# SpheroRemote.net
KiCad netlist of a schematic drawn in EAGLE
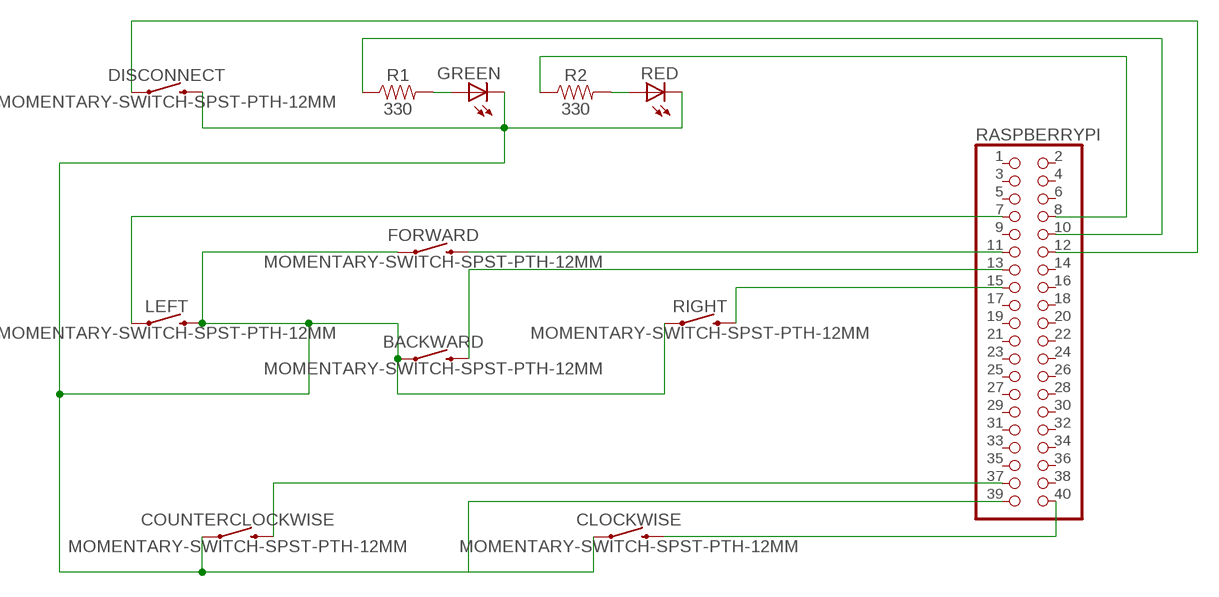
[diagram p0: schematic, sheet 1]

(export (version "E")
  (design (tool "Eeschema 10.0.6"))
  (components
    (comp (ref "BACKWARD")
      (value "MOMENTARY-SWITCH-SPST-PTH-12MM")
      (footprint "eagle-import:TACTILE_SWITCH_PTH_12MM")
      (libsource (lib "eagle-import") (part "MOMENTARY-SWITCH-SPST-PTH-12MM"))
    )
    (comp (ref "CLOCKWISE")
      (value "MOMENTARY-SWITCH-SPST-PTH-12MM")
      (footprint "eagle-import:TACTILE_SWITCH_PTH_12MM")
      (libsource (lib "eagle-import") (part "MOMENTARY-SWITCH-SPST-PTH-12MM"))
    )
    (comp (ref "COUNTERCLOCKWISE")
      (value "MOMENTARY-SWITCH-SPST-PTH-12MM")
      (footprint "eagle-import:TACTILE_SWITCH_PTH_12MM")
      (libsource (lib "eagle-import") (part "MOMENTARY-SWITCH-SPST-PTH-12MM"))
    )
    (comp (ref "DISCONNECT")
      (value "MOMENTARY-SWITCH-SPST-PTH-12MM")
      (footprint "eagle-import:TACTILE_SWITCH_PTH_12MM")
      (libsource (lib "eagle-import") (part "MOMENTARY-SWITCH-SPST-PTH-12MM"))
    )
    (comp (ref "FORWARD")
      (value "MOMENTARY-SWITCH-SPST-PTH-12MM")
      (footprint "eagle-import:TACTILE_SWITCH_PTH_12MM")
      (libsource (lib "eagle-import") (part "MOMENTARY-SWITCH-SPST-PTH-12MM"))
    )
    (comp (ref "GREEN")
      (value "LED5MM")
      (footprint "eagle-import:LED5MM")
      (libsource (lib "eagle-import") (part "LED5MM"))
    )
    (comp (ref "LEFT")
      (value "MOMENTARY-SWITCH-SPST-PTH-12MM")
      (footprint "eagle-import:TACTILE_SWITCH_PTH_12MM")
      (libsource (lib "eagle-import") (part "MOMENTARY-SWITCH-SPST-PTH-12MM"))
    )
    (comp (ref "R1")
      (value "330")
      (footprint "eagle-import:AXIAL-0.3")
      (libsource (lib "eagle-import") (part "330OHM-HORIZ-1/10W-5%"))
    )
    (comp (ref "R2")
      (value "330")
      (footprint "eagle-import:AXIAL-0.3")
      (libsource (lib "eagle-import") (part "330OHM-HORIZ-1/10W-5%"))
    )
    (comp (ref "RASPBERRYPI")
      (value "PINHD-2X20")
      (footprint "eagle-import:2X20")
      (libsource (lib "eagle-import") (part "PINHD-2X20"))
    )
    (comp (ref "RED")
      (value "LED5MM")
      (footprint "eagle-import:LED5MM")
      (libsource (lib "eagle-import") (part "LED5MM"))
    )
    (comp (ref "RIGHT")
      (value "MOMENTARY-SWITCH-SPST-PTH-12MM")
      (footprint "eagle-import:TACTILE_SWITCH_PTH_12MM")
      (libsource (lib "eagle-import") (part "MOMENTARY-SWITCH-SPST-PTH-12MM"))
    )
  )
  (nets
    (net (code "1") (name "Net-(BACKWARD-2)") (class "Default")
      (node (ref "BACKWARD") (pin "3") (pinfunction "2_3") (pintype "passive"))
      (node (ref "RASPBERRYPI") (pin "13") (pinfunction "13_13") (pintype "passive"))
    )
    (net (code "2") (name "Net-(CLOCKWISE-2)") (class "Default")
      (node (ref "CLOCKWISE") (pin "3") (pinfunction "2_3") (pintype "passive"))
      (node (ref "RASPBERRYPI") (pin "40") (pinfunction "40_40") (pintype "passive"))
    )
    (net (code "3") (name "Net-(COUNTERCLOCKWISE-2)") (class "Default")
      (node (ref "COUNTERCLOCKWISE") (pin "3") (pinfunction "2_3") (pintype "passive"))
      (node (ref "RASPBERRYPI") (pin "37") (pinfunction "37_37") (pintype "passive"))
    )
    (net (code "4") (name "Net-(DISCONNECT-2)") (class "Default")
      (node (ref "BACKWARD") (pin "1") (pinfunction "1_1") (pintype "passive"))
      (node (ref "CLOCKWISE") (pin "1") (pinfunction "1_1") (pintype "passive"))
      (node (ref "COUNTERCLOCKWISE") (pin "1") (pinfunction "1_1") (pintype "passive"))
      (node (ref "DISCONNECT") (pin "3") (pinfunction "2_3") (pintype "passive"))
      (node (ref "FORWARD") (pin "1") (pinfunction "1_1") (pintype "passive"))
      (node (ref "GREEN") (pin "K") (pinfunction "C_K") (pintype "passive"))
      (node (ref "LEFT") (pin "3") (pinfunction "2_3") (pintype "passive"))
      (node (ref "RASPBERRYPI") (pin "39") (pinfunction "39_39") (pintype "passive"))
      (node (ref "RED") (pin "K") (pinfunction "C_K") (pintype "passive"))
      (node (ref "RIGHT") (pin "1") (pinfunction "1_1") (pintype "passive"))
    )
    (net (code "5") (name "Net-(DISCONNECT-Pad1)") (class "Default")
      (node (ref "DISCONNECT") (pin "1") (pinfunction "1_1") (pintype "passive"))
      (node (ref "RASPBERRYPI") (pin "12") (pinfunction "12_12") (pintype "passive"))
    )
    (net (code "6") (name "Net-(FORWARD-2)") (class "Default")
      (node (ref "FORWARD") (pin "3") (pinfunction "2_3") (pintype "passive"))
      (node (ref "RASPBERRYPI") (pin "11") (pinfunction "11_11") (pintype "passive"))
    )
    (net (code "7") (name "Net-(LEFT-Pad1)") (class "Default")
      (node (ref "LEFT") (pin "1") (pinfunction "1_1") (pintype "passive"))
      (node (ref "RASPBERRYPI") (pin "7") (pinfunction "7_7") (pintype "passive"))
    )
    (net (code "8") (name "Net-(R1-1)") (class "Default")
      (node (ref "R1") (pin "P$1") (pinfunction "1_P$1") (pintype "passive"))
      (node (ref "RASPBERRYPI") (pin "10") (pinfunction "10_10") (pintype "passive"))
    )
    (net (code "9") (name "Net-(R1-2)") (class "Default")
      (node (ref "GREEN") (pin "A") (pinfunction "A_A") (pintype "passive"))
      (node (ref "R1") (pin "P$2") (pinfunction "2_P$2") (pintype "passive"))
    )
    (net (code "10") (name "Net-(R2-1)") (class "Default")
      (node (ref "R2") (pin "P$1") (pinfunction "1_P$1") (pintype "passive"))
      (node (ref "RASPBERRYPI") (pin "8") (pinfunction "8_8") (pintype "passive"))
    )
    (net (code "11") (name "Net-(R2-2)") (class "Default")
      (node (ref "R2") (pin "P$2") (pinfunction "2_P$2") (pintype "passive"))
      (node (ref "RED") (pin "A") (pinfunction "A_A") (pintype "passive"))
    )
    (net (code "12") (name "Net-(RIGHT-2)") (class "Default")
      (node (ref "RASPBERRYPI") (pin "15") (pinfunction "15_15") (pintype "passive"))
      (node (ref "RIGHT") (pin "3") (pinfunction "2_3") (pintype "passive"))
    )
    (net (code "13") (name "unconnected-(RASPBERRYPI-Pad1)") (class "Default")
      (node (ref "RASPBERRYPI") (pin "1") (pinfunction "1_1") (pintype "passive"))
    )
    (net (code "14") (name "unconnected-(RASPBERRYPI-Pad2)") (class "Default")
      (node (ref "RASPBERRYPI") (pin "2") (pinfunction "2_2") (pintype "passive"))
    )
    (net (code "15") (name "unconnected-(RASPBERRYPI-Pad3)") (class "Default")
      (node (ref "RASPBERRYPI") (pin "3") (pinfunction "3_3") (pintype "passive"))
    )
    (net (code "16") (name "unconnected-(RASPBERRYPI-Pad4)") (class "Default")
      (node (ref "RASPBERRYPI") (pin "4") (pinfunction "4_4") (pintype "passive"))
    )
    (net (code "17") (name "unconnected-(RASPBERRYPI-Pad5)") (class "Default")
      (node (ref "RASPBERRYPI") (pin "5") (pinfunction "5_5") (pintype "passive"))
    )
    (net (code "18") (name "unconnected-(RASPBERRYPI-Pad6)") (class "Default")
      (node (ref "RASPBERRYPI") (pin "6") (pinfunction "6_6") (pintype "passive"))
    )
    (net (code "19") (name "unconnected-(RASPBERRYPI-Pad9)") (class "Default")
      (node (ref "RASPBERRYPI") (pin "9") (pinfunction "9_9") (pintype "passive"))
    )
    (net (code "20") (name "unconnected-(RASPBERRYPI-Pad14)") (class "Default")
      (node (ref "RASPBERRYPI") (pin "14") (pinfunction "14_14") (pintype "passive"))
    )
    (net (code "21") (name "unconnected-(RASPBERRYPI-Pad16)") (class "Default")
      (node (ref "RASPBERRYPI") (pin "16") (pinfunction "16_16") (pintype "passive"))
    )
    (net (code "22") (name "unconnected-(RASPBERRYPI-Pad17)") (class "Default")
      (node (ref "RASPBERRYPI") (pin "17") (pinfunction "17_17") (pintype "passive"))
    )
    (net (code "23") (name "unconnected-(RASPBERRYPI-Pad18)") (class "Default")
      (node (ref "RASPBERRYPI") (pin "18") (pinfunction "18_18") (pintype "passive"))
    )
    (net (code "24") (name "unconnected-(RASPBERRYPI-Pad19)") (class "Default")
      (node (ref "RASPBERRYPI") (pin "19") (pinfunction "19_19") (pintype "passive"))
    )
    (net (code "25") (name "unconnected-(RASPBERRYPI-Pad20)") (class "Default")
      (node (ref "RASPBERRYPI") (pin "20") (pinfunction "20_20") (pintype "passive"))
    )
    (net (code "26") (name "unconnected-(RASPBERRYPI-Pad21)") (class "Default")
      (node (ref "RASPBERRYPI") (pin "21") (pinfunction "21_21") (pintype "passive"))
    )
    (net (code "27") (name "unconnected-(RASPBERRYPI-Pad22)") (class "Default")
      (node (ref "RASPBERRYPI") (pin "22") (pinfunction "22_22") (pintype "passive"))
    )
    (net (code "28") (name "unconnected-(RASPBERRYPI-Pad23)") (class "Default")
      (node (ref "RASPBERRYPI") (pin "23") (pinfunction "23_23") (pintype "passive"))
    )
    (net (code "29") (name "unconnected-(RASPBERRYPI-Pad24)") (class "Default")
      (node (ref "RASPBERRYPI") (pin "24") (pinfunction "24_24") (pintype "passive"))
    )
    (net (code "30") (name "unconnected-(RASPBERRYPI-Pad25)") (class "Default")
      (node (ref "RASPBERRYPI") (pin "25") (pinfunction "25_25") (pintype "passive"))
    )
    (net (code "31") (name "unconnected-(RASPBERRYPI-Pad26)") (class "Default")
      (node (ref "RASPBERRYPI") (pin "26") (pinfunction "26_26") (pintype "passive"))
    )
    (net (code "32") (name "unconnected-(RASPBERRYPI-Pad27)") (class "Default")
      (node (ref "RASPBERRYPI") (pin "27") (pinfunction "27_27") (pintype "passive"))
    )
    (net (code "33") (name "unconnected-(RASPBERRYPI-Pad28)") (class "Default")
      (node (ref "RASPBERRYPI") (pin "28") (pinfunction "28_28") (pintype "passive"))
    )
    (net (code "34") (name "unconnected-(RASPBERRYPI-Pad29)") (class "Default")
      (node (ref "RASPBERRYPI") (pin "29") (pinfunction "29_29") (pintype "passive"))
    )
    (net (code "35") (name "unconnected-(RASPBERRYPI-Pad30)") (class "Default")
      (node (ref "RASPBERRYPI") (pin "30") (pinfunction "30_30") (pintype "passive"))
    )
    (net (code "36") (name "unconnected-(RASPBERRYPI-Pad31)") (class "Default")
      (node (ref "RASPBERRYPI") (pin "31") (pinfunction "31_31") (pintype "passive"))
    )
    (net (code "37") (name "unconnected-(RASPBERRYPI-Pad32)") (class "Default")
      (node (ref "RASPBERRYPI") (pin "32") (pinfunction "32_32") (pintype "passive"))
    )
    (net (code "38") (name "unconnected-(RASPBERRYPI-Pad33)") (class "Default")
      (node (ref "RASPBERRYPI") (pin "33") (pinfunction "33_33") (pintype "passive"))
    )
    (net (code "39") (name "unconnected-(RASPBERRYPI-Pad34)") (class "Default")
      (node (ref "RASPBERRYPI") (pin "34") (pinfunction "34_34") (pintype "passive"))
    )
    (net (code "40") (name "unconnected-(RASPBERRYPI-Pad35)") (class "Default")
      (node (ref "RASPBERRYPI") (pin "35") (pinfunction "35_35") (pintype "passive"))
    )
    (net (code "41") (name "unconnected-(RASPBERRYPI-Pad36)") (class "Default")
      (node (ref "RASPBERRYPI") (pin "36") (pinfunction "36_36") (pintype "passive"))
    )
    (net (code "42") (name "unconnected-(RASPBERRYPI-Pad38)") (class "Default")
      (node (ref "RASPBERRYPI") (pin "38") (pinfunction "38_38") (pintype "passive"))
    )
  )
)
